# simcovox_atmega.net
KiCad netlist of a schematic drawn in EAGLE
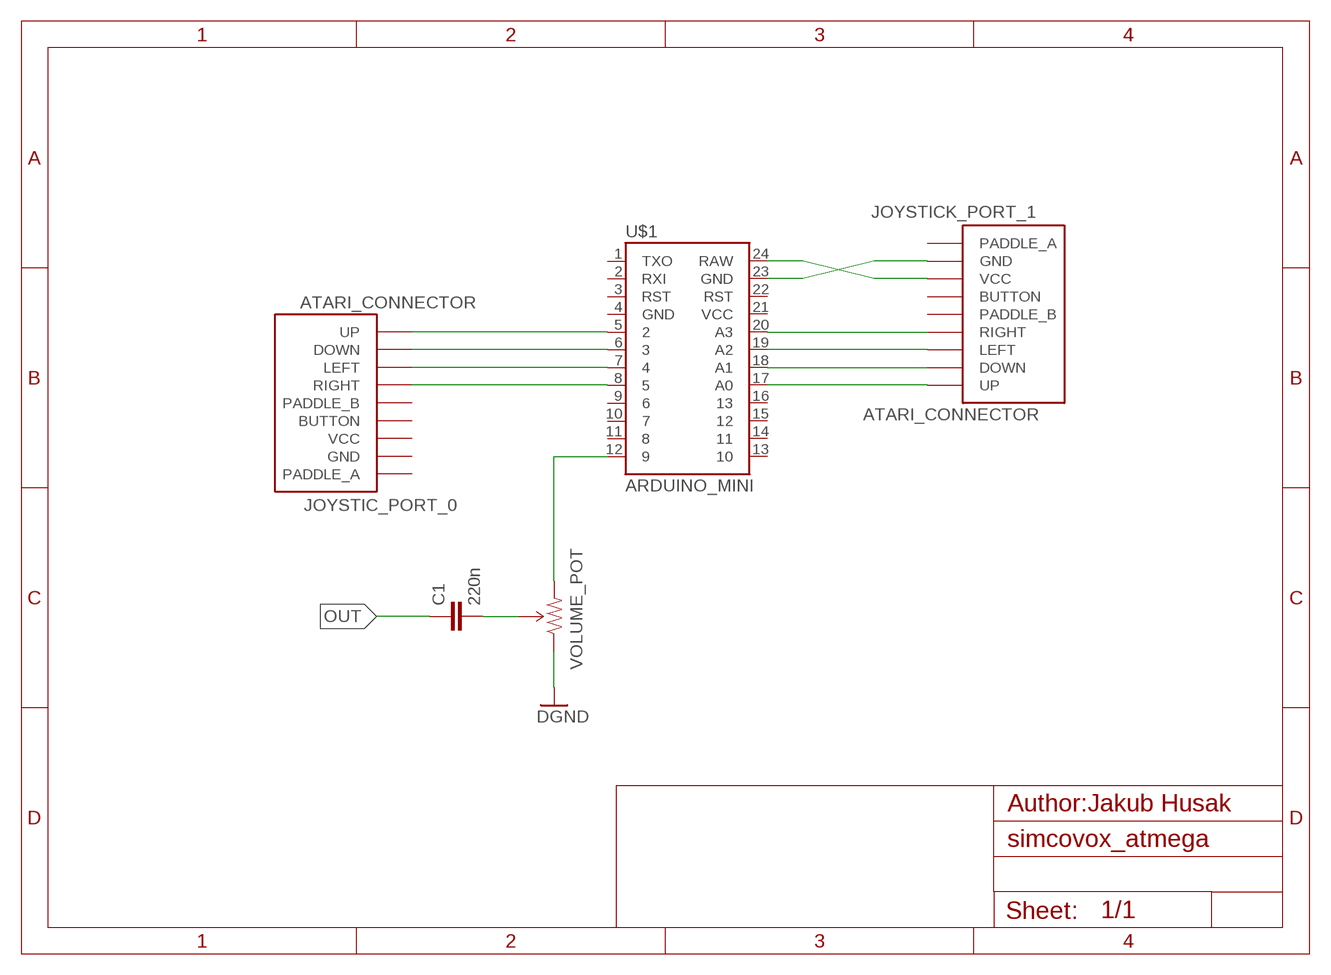
[diagram p0: schematic, sheet 1]

(export (version "E")
  (design (tool "Eeschema 10.0.6"))
  (components
    (comp (ref "C1")
      (value "220n")
      (footprint "eagle-import:CAP-PTH-SMALL-KIT")
      (libsource (lib "eagle-import") (part "CAPKIT"))
    )
    (comp (ref "JOYSTICK_PORT_1")
      (value "ATARI_CONNECTOR")
      (footprint "eagle-import:ATARI_CONNECTOR")
      (libsource (lib "eagle-import") (part "ATARI_CONNECTOR"))
    )
    (comp (ref "JOYSTIC_PORT_0")
      (value "ATARI_CONNECTOR")
      (footprint "eagle-import:ATARI_CONNECTOR")
      (libsource (lib "eagle-import") (part "ATARI_CONNECTOR"))
    )
    (comp (ref "U$1")
      (value "ARDUINO_MINI")
      (footprint "eagle-import:ARDUINO_MINI")
      (libsource (lib "eagle-import") (part "ARDUINO_MINI"))
    )
    (comp (ref "VOLUME_POT")
      (value "TRIMPOTPTH")
      (footprint "eagle-import:TRIM_POT_PTH")
      (libsource (lib "eagle-import") (part "TRIMPOTPTH"))
    )
  )
  (nets
    (net (code "1") (name "DGND") (class "Default")
      (node (ref "VOLUME_POT") (pin "1") (pinfunction "CCW_1") (pintype "passive"))
    )
    (net (code "2") (name "Net-(JOYSTICK_PORT_1-DOWN)") (class "Default")
      (node (ref "JOYSTICK_PORT_1") (pin "P$6") (pinfunction "DOWN_P$6") (pintype "bidirectional"))
      (node (ref "U$1") (pin "18") (pinfunction "A1_18") (pintype "bidirectional"))
    )
    (net (code "3") (name "Net-(JOYSTICK_PORT_1-GND)") (class "Default")
      (node (ref "JOYSTICK_PORT_1") (pin "P$3") (pinfunction "GND_P$3") (pintype "bidirectional"))
      (node (ref "U$1") (pin "23") (pinfunction "GND_23") (pintype "bidirectional"))
    )
    (net (code "4") (name "Net-(JOYSTICK_PORT_1-LEFT)") (class "Default")
      (node (ref "JOYSTICK_PORT_1") (pin "P$7") (pinfunction "LEFT_P$7") (pintype "bidirectional"))
      (node (ref "U$1") (pin "19") (pinfunction "A2_19") (pintype "bidirectional"))
    )
    (net (code "5") (name "Net-(JOYSTICK_PORT_1-RIGHT)") (class "Default")
      (node (ref "JOYSTICK_PORT_1") (pin "P$8") (pinfunction "RIGHT_P$8") (pintype "bidirectional"))
      (node (ref "U$1") (pin "20") (pinfunction "A3_20") (pintype "bidirectional"))
    )
    (net (code "6") (name "Net-(JOYSTICK_PORT_1-UP)") (class "Default")
      (node (ref "JOYSTICK_PORT_1") (pin "P$5") (pinfunction "UP_P$5") (pintype "bidirectional"))
      (node (ref "U$1") (pin "17") (pinfunction "A0_17") (pintype "bidirectional"))
    )
    (net (code "7") (name "Net-(JOYSTICK_PORT_1-VCC)") (class "Default")
      (node (ref "JOYSTICK_PORT_1") (pin "P$2") (pinfunction "VCC_P$2") (pintype "bidirectional"))
      (node (ref "U$1") (pin "24") (pinfunction "RAW_24") (pintype "bidirectional"))
    )
    (net (code "8") (name "Net-(JOYSTIC_PORT_0-DOWN)") (class "Default")
      (node (ref "JOYSTIC_PORT_0") (pin "P$6") (pinfunction "DOWN_P$6") (pintype "bidirectional"))
      (node (ref "U$1") (pin "6") (pinfunction "3_6") (pintype "bidirectional"))
    )
    (net (code "9") (name "Net-(JOYSTIC_PORT_0-LEFT)") (class "Default")
      (node (ref "JOYSTIC_PORT_0") (pin "P$7") (pinfunction "LEFT_P$7") (pintype "bidirectional"))
      (node (ref "U$1") (pin "7") (pinfunction "4_7") (pintype "bidirectional"))
    )
    (net (code "10") (name "Net-(JOYSTIC_PORT_0-RIGHT)") (class "Default")
      (node (ref "JOYSTIC_PORT_0") (pin "P$8") (pinfunction "RIGHT_P$8") (pintype "bidirectional"))
      (node (ref "U$1") (pin "8") (pinfunction "5_8") (pintype "bidirectional"))
    )
    (net (code "11") (name "Net-(JOYSTIC_PORT_0-UP)") (class "Default")
      (node (ref "JOYSTIC_PORT_0") (pin "P$5") (pinfunction "UP_P$5") (pintype "bidirectional"))
      (node (ref "U$1") (pin "5") (pinfunction "2_5") (pintype "bidirectional"))
    )
    (net (code "12") (name "Net-(U$1-9)") (class "Default")
      (node (ref "U$1") (pin "12") (pinfunction "9_12") (pintype "bidirectional"))
      (node (ref "VOLUME_POT") (pin "3") (pinfunction "CW_3") (pintype "passive"))
    )
    (net (code "13") (name "Net-(VOLUME_POT-WIPER)") (class "Default")
      (node (ref "C1") (pin "2") (pinfunction "2_2") (pintype "passive"))
      (node (ref "VOLUME_POT") (pin "2") (pinfunction "WIPER_2") (pintype "passive"))
    )
    (net (code "14") (name "OUT") (class "Default")
      (node (ref "C1") (pin "1") (pinfunction "1_1") (pintype "passive"))
    )
    (net (code "15") (name "unconnected-(JOYSTICK_PORT_1-BUTTON-PadP$1)") (class "Default")
      (node (ref "JOYSTICK_PORT_1") (pin "P$1") (pinfunction "BUTTON_P$1") (pintype "bidirectional"))
    )
    (net (code "16") (name "unconnected-(JOYSTICK_PORT_1-PADDLE_A-PadP$4)") (class "Default")
      (node (ref "JOYSTICK_PORT_1") (pin "P$4") (pinfunction "PADDLE_A_P$4") (pintype "bidirectional"))
    )
    (net (code "17") (name "unconnected-(JOYSTICK_PORT_1-PADDLE_B-PadP$9)") (class "Default")
      (node (ref "JOYSTICK_PORT_1") (pin "P$9") (pinfunction "PADDLE_B_P$9") (pintype "bidirectional"))
    )
    (net (code "18") (name "unconnected-(JOYSTIC_PORT_0-BUTTON-PadP$1)") (class "Default")
      (node (ref "JOYSTIC_PORT_0") (pin "P$1") (pinfunction "BUTTON_P$1") (pintype "bidirectional"))
    )
    (net (code "19") (name "unconnected-(JOYSTIC_PORT_0-GND-PadP$3)") (class "Default")
      (node (ref "JOYSTIC_PORT_0") (pin "P$3") (pinfunction "GND_P$3") (pintype "bidirectional"))
    )
    (net (code "20") (name "unconnected-(JOYSTIC_PORT_0-PADDLE_A-PadP$4)") (class "Default")
      (node (ref "JOYSTIC_PORT_0") (pin "P$4") (pinfunction "PADDLE_A_P$4") (pintype "bidirectional"))
    )
    (net (code "21") (name "unconnected-(JOYSTIC_PORT_0-PADDLE_B-PadP$9)") (class "Default")
      (node (ref "JOYSTIC_PORT_0") (pin "P$9") (pinfunction "PADDLE_B_P$9") (pintype "bidirectional"))
    )
    (net (code "22") (name "unconnected-(JOYSTIC_PORT_0-VCC-PadP$2)") (class "Default")
      (node (ref "JOYSTIC_PORT_0") (pin "P$2") (pinfunction "VCC_P$2") (pintype "bidirectional"))
    )
    (net (code "23") (name "unconnected-(U$1-6-Pad9)") (class "Default")
      (node (ref "U$1") (pin "9") (pinfunction "6_9") (pintype "bidirectional"))
    )
    (net (code "24") (name "unconnected-(U$1-7-Pad10)") (class "Default")
      (node (ref "U$1") (pin "10") (pinfunction "7_10") (pintype "bidirectional"))
    )
    (net (code "25") (name "unconnected-(U$1-8-Pad11)") (class "Default")
      (node (ref "U$1") (pin "11") (pinfunction "8_11") (pintype "bidirectional"))
    )
    (net (code "26") (name "unconnected-(U$1-10-Pad13)") (class "Default")
      (node (ref "U$1") (pin "13") (pinfunction "10_13") (pintype "bidirectional"))
    )
    (net (code "27") (name "unconnected-(U$1-11-Pad14)") (class "Default")
      (node (ref "U$1") (pin "14") (pinfunction "11_14") (pintype "bidirectional"))
    )
    (net (code "28") (name "unconnected-(U$1-12-Pad15)") (class "Default")
      (node (ref "U$1") (pin "15") (pinfunction "12_15") (pintype "bidirectional"))
    )
    (net (code "29") (name "unconnected-(U$1-13-Pad16)") (class "Default")
      (node (ref "U$1") (pin "16") (pinfunction "13_16") (pintype "bidirectional"))
    )
    (net (code "30") (name "unconnected-(U$1-GND-Pad4)") (class "Default")
      (node (ref "U$1") (pin "4") (pinfunction "GND_4") (pintype "bidirectional"))
    )
    (net (code "31") (name "unconnected-(U$1-RST-Pad3)") (class "Default")
      (node (ref "U$1") (pin "3") (pinfunction "RST_3") (pintype "bidirectional"))
    )
    (net (code "32") (name "unconnected-(U$1-RST-Pad22)") (class "Default")
      (node (ref "U$1") (pin "22") (pinfunction "RST_22") (pintype "bidirectional"))
    )
    (net (code "33") (name "unconnected-(U$1-RXI-Pad2)") (class "Default")
      (node (ref "U$1") (pin "2") (pinfunction "RXI_2") (pintype "bidirectional"))
    )
    (net (code "34") (name "unconnected-(U$1-TXO-Pad1)") (class "Default")
      (node (ref "U$1") (pin "1") (pinfunction "TXO_1") (pintype "bidirectional"))
    )
    (net (code "35") (name "unconnected-(U$1-VCC-Pad21)") (class "Default")
      (node (ref "U$1") (pin "21") (pinfunction "VCC_21") (pintype "bidirectional"))
    )
  )
)
